# BSPD.net
KiCad netlist of a schematic drawn in Altium Designer
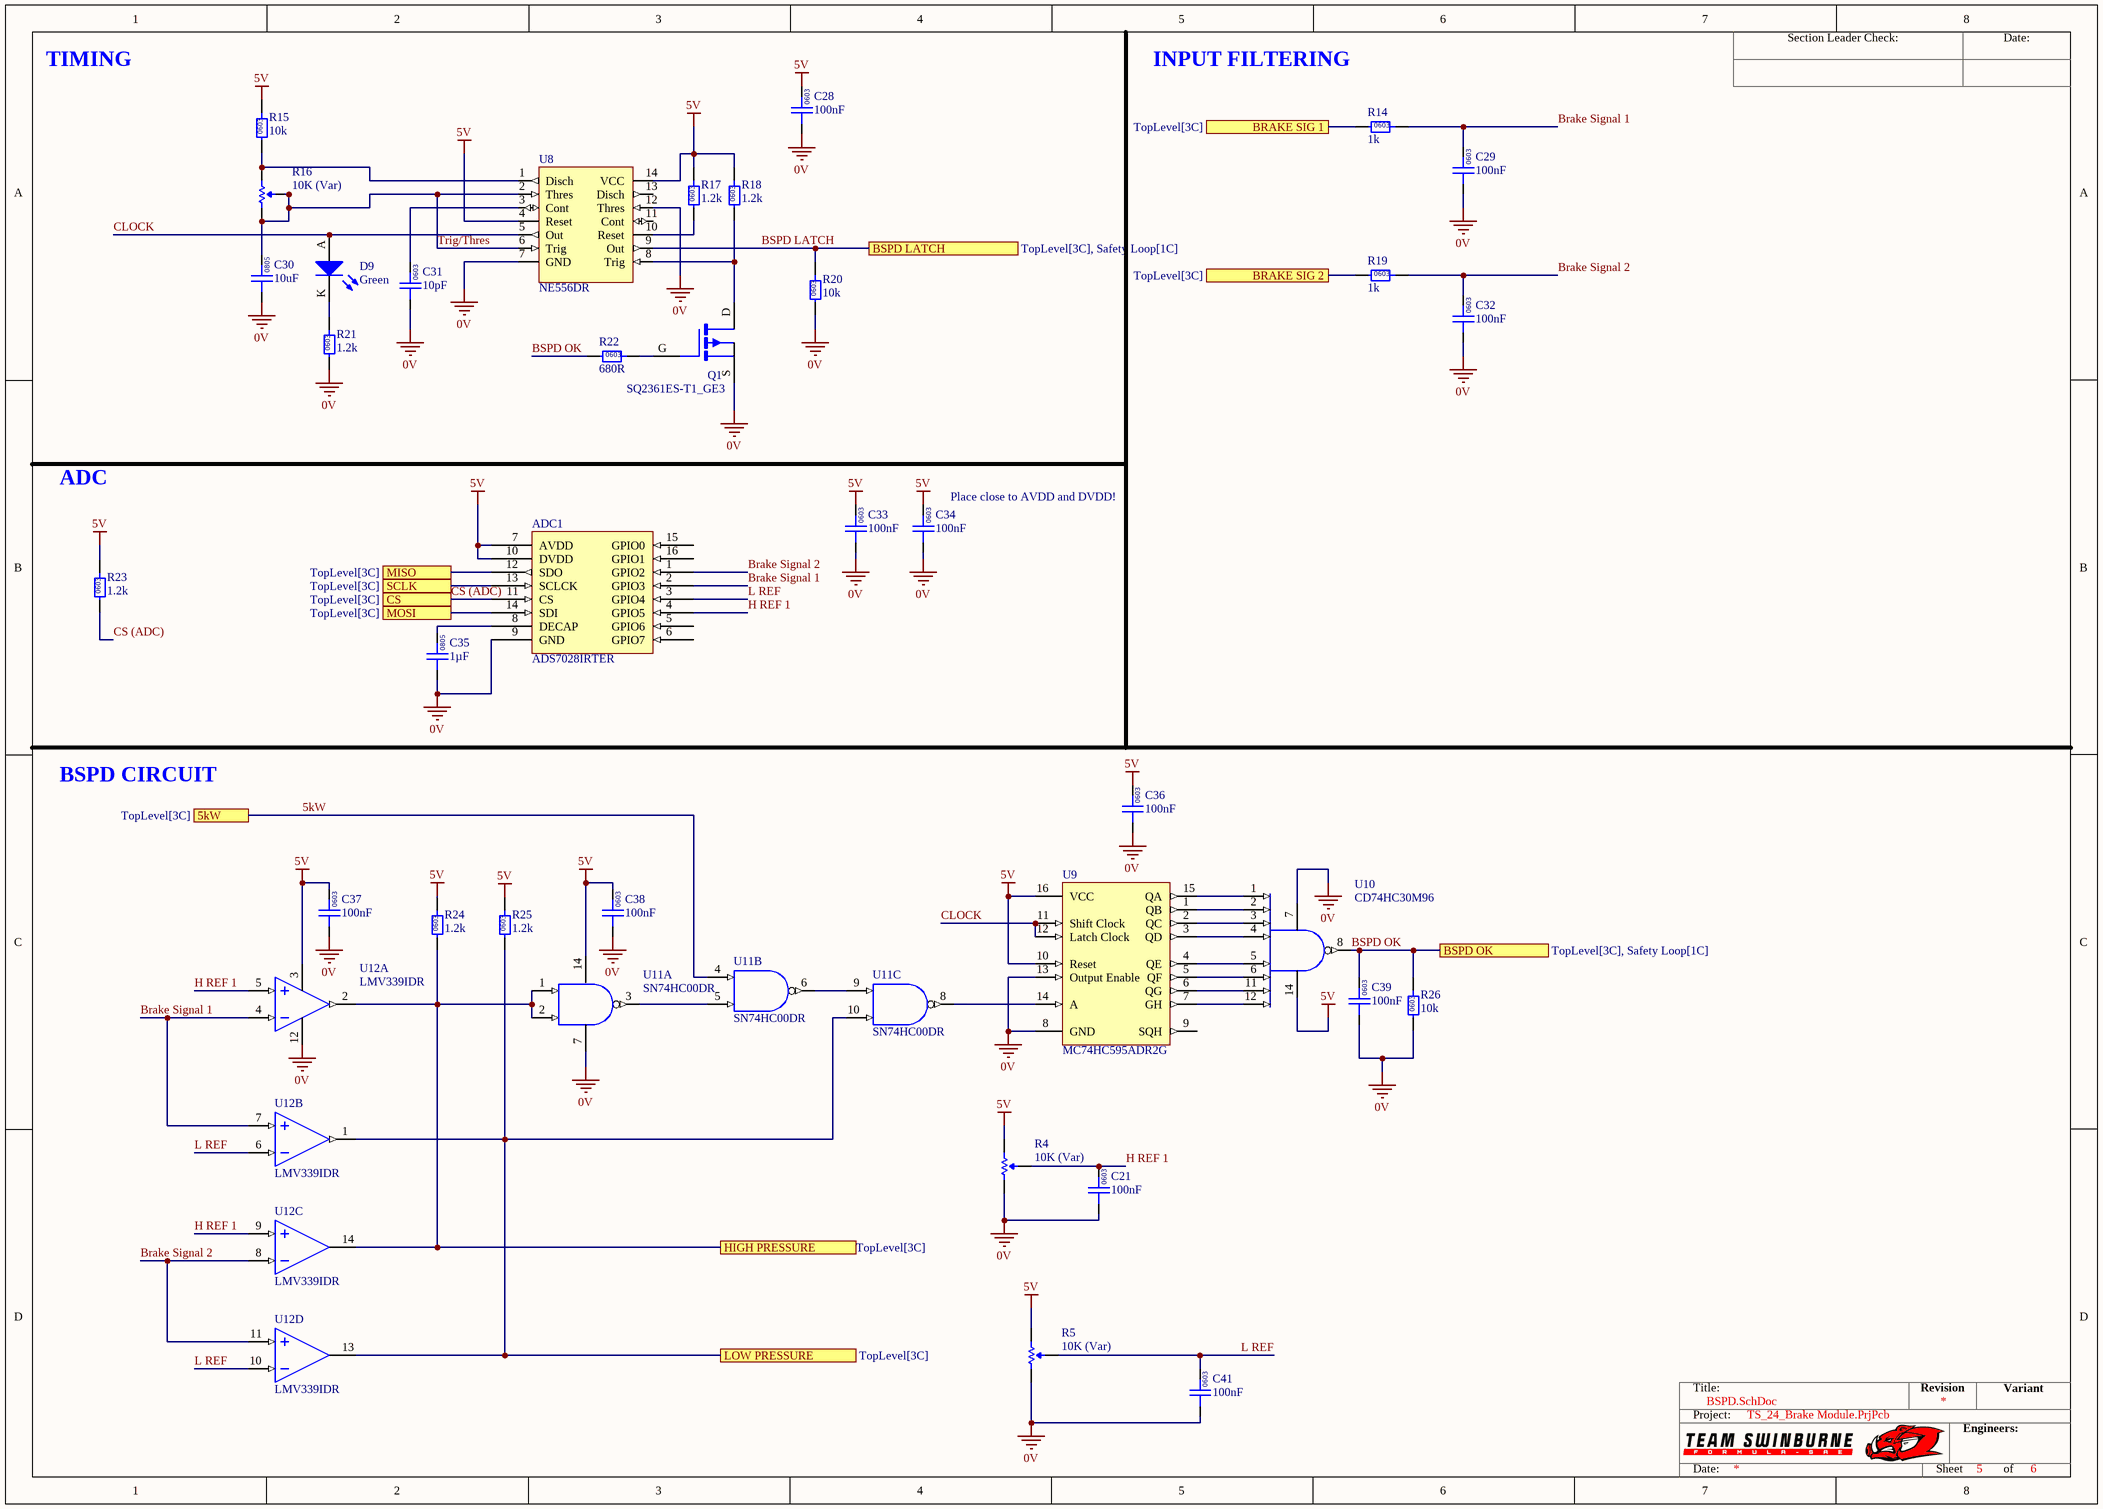
[diagram p0: BSPD.SchDoc]

(export (version "E")
  (design (tool "Eeschema 10.0.6"))
  (components
    (comp (ref "ADC1")
      (value "ADS7028IRTER")
      (footprint "WFQN-16")
      (description "IC ADC 12BIT SAR 16WQFN")
      (fields (field (name "MANUFACTURER") "Texas Instruments"))
      (libsource (lib "ts_standard_library") (part "ADS7028IRTER"))
    )
    (comp (ref "C21")
      (value "100nF")
      (footprint "0603")
      (fields
        (field (name "PART NUMBER") "GCM188L81H104KA57D")
        (field (name "MANUFACTURER") "muRata")
        (field (name "TOLERANCE") "±10%")
      )
      (libsource (lib "ts_standard_library") (part "Capacitor 0603"))
    )
    (comp (ref "C28")
      (value "100nF")
      (footprint "0603")
      (fields
        (field (name "PART NUMBER") "GCM188L81H104KA57D")
        (field (name "MANUFACTURER") "muRata")
        (field (name "TOLERANCE") "±10%")
      )
      (libsource (lib "ts_standard_library") (part "Capacitor 0603"))
    )
    (comp (ref "C29")
      (value "100nF")
      (footprint "0603")
      (fields
        (field (name "PART NUMBER") "GCM188L81H104KA57D")
        (field (name "MANUFACTURER") "muRata")
        (field (name "TOLERANCE") "±10%")
      )
      (libsource (lib "ts_standard_library") (part "Capacitor 0603"))
    )
    (comp (ref "C30")
      (value "10uF")
      (footprint "0805")
      (fields
        (field (name "PART NUMBER") "GRM21BR6YA106KE43L")
        (field (name "MANUFACTURER") "muRata")
        (field (name "TOLERANCE") "10%")
      )
      (libsource (lib "ts_standard_library") (part "Capacitor 0805"))
    )
    (comp (ref "C31")
      (value "10pF")
      (footprint "0603")
      (fields
        (field (name "PART NUMBER") "GRM1885C1H100JA01D")
        (field (name "MANUFACTURER") "Murata Electronics")
        (field (name "TOLERANCE") "±5%")
      )
      (libsource (lib "ts_standard_library") (part "Capacitor 0603"))
    )
    (comp (ref "C32")
      (value "100nF")
      (footprint "0603")
      (fields
        (field (name "PART NUMBER") "GCM188L81H104KA57D")
        (field (name "MANUFACTURER") "muRata")
        (field (name "TOLERANCE") "±10%")
      )
      (libsource (lib "ts_standard_library") (part "Capacitor 0603"))
    )
    (comp (ref "C33")
      (value "100nF")
      (footprint "0603")
      (fields
        (field (name "PART NUMBER") "GCM188L81H104KA57D")
        (field (name "MANUFACTURER") "muRata")
        (field (name "TOLERANCE") "±10%")
      )
      (libsource (lib "ts_standard_library") (part "Capacitor 0603"))
    )
    (comp (ref "C34")
      (value "100nF")
      (footprint "0603")
      (fields
        (field (name "PART NUMBER") "GCM188L81H104KA57D")
        (field (name "MANUFACTURER") "muRata")
        (field (name "TOLERANCE") "±10%")
      )
      (libsource (lib "ts_standard_library") (part "Capacitor 0603"))
    )
    (comp (ref "C35")
      (value "1µF")
      (footprint "0805")
      (fields
        (field (name "PART NUMBER") "GCM21BR71H105KA03L")
        (field (name "MANUFACTURER") "muRata")
        (field (name "TOLERANCE") "±10%")
      )
      (libsource (lib "ts_standard_library") (part "Capacitor 0805"))
    )
    (comp (ref "C36")
      (value "100nF")
      (footprint "0603")
      (fields
        (field (name "PART NUMBER") "GCM188L81H104KA57D")
        (field (name "MANUFACTURER") "muRata")
        (field (name "TOLERANCE") "±10%")
      )
      (libsource (lib "ts_standard_library") (part "Capacitor 0603"))
    )
    (comp (ref "C37")
      (value "100nF")
      (footprint "0603")
      (fields
        (field (name "PART NUMBER") "GCM188L81H104KA57D")
        (field (name "MANUFACTURER") "muRata")
        (field (name "TOLERANCE") "±10%")
      )
      (libsource (lib "ts_standard_library") (part "Capacitor 0603"))
    )
    (comp (ref "C38")
      (value "100nF")
      (footprint "0603")
      (fields
        (field (name "PART NUMBER") "GCM188L81H104KA57D")
        (field (name "MANUFACTURER") "muRata")
        (field (name "TOLERANCE") "±10%")
      )
      (libsource (lib "ts_standard_library") (part "Capacitor 0603"))
    )
    (comp (ref "C39")
      (value "100nF")
      (footprint "0603")
      (fields
        (field (name "PART NUMBER") "GCM188L81H104KA57D")
        (field (name "MANUFACTURER") "muRata")
        (field (name "TOLERANCE") "±10%")
      )
      (libsource (lib "ts_standard_library") (part "Capacitor 0603"))
    )
    (comp (ref "C41")
      (value "100nF")
      (footprint "0603")
      (fields
        (field (name "PART NUMBER") "GCM188L81H104KA57D")
        (field (name "MANUFACTURER") "muRata")
        (field (name "TOLERANCE") "±10%")
      )
      (libsource (lib "ts_standard_library") (part "Capacitor 0603"))
    )
    (comp (ref "D9")
      (value "Green")
      (footprint "0805 LED")
      (description "Green LED Indication - Discrete 1.75V 0805 (2012 Metric)")
      (fields (field (name "PART NUMBER") "SML-210FTT86") (field (name "MANUFACTURER") "ROHM Semiconductor"))
      (libsource (lib "ts_standard_library") (part "LED"))
    )
    (comp (ref "Q1")
      (value "SQ2361ES-T1_GE3")
      (footprint "VSHY SOT-23-3")
      (description "MOSFET P-CH 60V 2.8A SSOT23")
      (fields
        (field (name "MANUFACTURER") "Vishay Siliconix")
        (field (name "DIGIKEY PART NUMBER") "SQ2361ES-T1_GE3CT-ND")
        (field (name "PUBLISHER") "Altium Limited")
      )
      (libsource (lib "ts_standard_library") (part "MOSFET-P"))
    )
    (comp (ref "R4")
      (value "10K (Var)")
      (footprint "3339P-1-1103LF")
      (fields
        (field (name "PART NUMBER") "3339P-1-1103LF")
        (field (name "MANUFACTURER") "Bournes Inc")
        (field (name "TOLERANCE") "0.1")
      )
      (libsource (lib "ts_standard_library") (part "Resistor (Potentiometer)"))
    )
    (comp (ref "R5")
      (value "10K (Var)")
      (footprint "3339P-1-1103LF")
      (fields
        (field (name "PART NUMBER") "3339P-1-1103LF")
        (field (name "MANUFACTURER") "Bournes Inc")
        (field (name "TOLERANCE") "0.1")
      )
      (libsource (lib "ts_standard_library") (part "Resistor (Potentiometer)"))
    )
    (comp (ref "R14")
      (value "1k")
      (footprint "0603")
      (fields
        (field (name "PART NUMBER") "RC0603FR-071KL")
        (field (name "MANUFACTURER") "YAGEO")
        (field (name "TOLERANCE") "0.01")
      )
      (libsource (lib "ts_standard_library") (part "Resistor 0603"))
    )
    (comp (ref "R15")
      (value "10k")
      (footprint "0603")
      (fields
        (field (name "PART NUMBER") "RC0603FR-0710KL")
        (field (name "MANUFACTURER") "YAGEO")
        (field (name "TOLERANCE") "0.01")
      )
      (libsource (lib "ts_standard_library") (part "Resistor 0603"))
    )
    (comp (ref "R16")
      (value "10K (Var)")
      (footprint "B 3296")
      (fields
        (field (name "PART NUMBER") "3296W-1-103LF")
        (field (name "MANUFACTURER") "Bournes Inc")
        (field (name "TOLERANCE") "0.1")
      )
      (libsource (lib "ts_standard_library") (part "Resistor (Potentiometer)"))
    )
    (comp (ref "R17")
      (value "1.2k")
      (footprint "0603")
      (fields
        (field (name "PART NUMBER") "RC0603JR-071K2L")
        (field (name "MANUFACTURER") "YAGEO")
        (field (name "TOLERANCE") "0.01")
      )
      (libsource (lib "ts_standard_library") (part "Resistor 0603"))
    )
    (comp (ref "R18")
      (value "1.2k")
      (footprint "0603")
      (fields
        (field (name "PART NUMBER") "RC0603JR-071K2L")
        (field (name "MANUFACTURER") "YAGEO")
        (field (name "TOLERANCE") "0.01")
      )
      (libsource (lib "ts_standard_library") (part "Resistor 0603"))
    )
    (comp (ref "R19")
      (value "1k")
      (footprint "0603")
      (fields
        (field (name "PART NUMBER") "RC0603FR-071KL")
        (field (name "MANUFACTURER") "YAGEO")
        (field (name "TOLERANCE") "0.01")
      )
      (libsource (lib "ts_standard_library") (part "Resistor 0603"))
    )
    (comp (ref "R20")
      (value "10k")
      (footprint "0603")
      (fields
        (field (name "PART NUMBER") "RC0603FR-0710KL")
        (field (name "MANUFACTURER") "YAGEO")
        (field (name "TOLERANCE") "0.01")
      )
      (libsource (lib "ts_standard_library") (part "Resistor 0603"))
    )
    (comp (ref "R21")
      (value "1.2k")
      (footprint "0603")
      (fields
        (field (name "PART NUMBER") "RC0603JR-071K2L")
        (field (name "MANUFACTURER") "YAGEO")
        (field (name "TOLERANCE") "0.01")
      )
      (libsource (lib "ts_standard_library") (part "Resistor 0603"))
    )
    (comp (ref "R22")
      (value "680R")
      (footprint "0603")
      (fields
        (field (name "PART NUMBER") "RC0603JR-13680RL")
        (field (name "MANUFACTURER") "YAGEO")
        (field (name "TOLERANCE") "0.01")
      )
      (libsource (lib "ts_standard_library") (part "Resistor 0603"))
    )
    (comp (ref "R23")
      (value "1.2k")
      (footprint "0603")
      (fields
        (field (name "PART NUMBER") "RC0603JR-071K2L")
        (field (name "MANUFACTURER") "YAGEO")
        (field (name "TOLERANCE") "0.01")
      )
      (libsource (lib "ts_standard_library") (part "Resistor 0603"))
    )
    (comp (ref "R24")
      (value "1.2k")
      (footprint "0603")
      (fields
        (field (name "PART NUMBER") "RC0603JR-071K2L")
        (field (name "MANUFACTURER") "YAGEO")
        (field (name "TOLERANCE") "0.01")
      )
      (libsource (lib "ts_standard_library") (part "Resistor 0603"))
    )
    (comp (ref "R25")
      (value "1.2k")
      (footprint "0603")
      (fields
        (field (name "PART NUMBER") "RC0603JR-071K2L")
        (field (name "MANUFACTURER") "YAGEO")
        (field (name "TOLERANCE") "0.01")
      )
      (libsource (lib "ts_standard_library") (part "Resistor 0603"))
    )
    (comp (ref "R26")
      (value "10k")
      (footprint "0603")
      (fields
        (field (name "PART NUMBER") "RC0603FR-0710KL")
        (field (name "MANUFACTURER") "YAGEO")
        (field (name "TOLERANCE") "0.01")
      )
      (libsource (lib "ts_standard_library") (part "Resistor 0603"))
    )
    (comp (ref "U8")
      (value "NE556DR")
      (footprint "TI-SOIC14")
      (description "IC OSC TIMER DUAL 100KHZ 14SOIC")
      (fields
        (field (name "MANUFACTURER") "Texas Instruments")
        (field (name "DIGIKEY PART NUMBER") "296-26240-1-ND")
      )
      (libsource (lib "ts_standard_library") (part "NE556DR"))
    )
    (comp (ref "U9")
      (value "MC74HC595ADR2G")
      (footprint "ON 16-SOIC")
      (description "IC SHIFT REGISTR 8BIT 3ST 16SOIC")
      (libsource (lib "Team Swinburne") (part "MC74HC595ADR2G"))
    )
    (comp (ref "U10")
      (value "CD74HC30M96")
      (footprint "TI 14-SOIC")
      (description "IC GATE NAND 1CH 8-INP 14SOIC")
      (libsource (lib "Team Swinburne") (part "CD74HC30M96"))
    )
    (comp (ref "U11")
      (value "SN74HC00DR")
      (footprint "TI 14-SOIC")
      (description "NAND Gate IC 4 Channel 14-SOIC")
      (libsource (lib "Team Swinburne") (part "SN74HC00DR"))
    )
    (comp (ref "U12")
      (value "LMV339IDR")
      (footprint "TI 14-SOIC")
      (description "Comparator General Purpose Open Collector 14-SOIC")
      (libsource (lib "Team Swinburne") (part "LMV339IDR"))
    )
  )
  (nets
    (net (code "1") (name "/5kW") (class "Default")
      (node (ref "U11") (pin "4") (pinfunction "2A_4") (pintype "input"))
    )
    (net (code "2") (name "/BRAKE SIG 1") (class "Default")
      (node (ref "R14") (pin "1") (pinfunction "1_1") (pintype "passive"))
    )
    (net (code "3") (name "/BRAKE SIG 2") (class "Default")
      (node (ref "R19") (pin "1") (pinfunction "1_1") (pintype "passive"))
    )
    (net (code "4") (name "/BSPD LATCH") (class "Default")
      (node (ref "R20") (pin "2") (pinfunction "2_2") (pintype "passive"))
      (node (ref "U8") (pin "9") (pinfunction "Out_9") (pintype "output"))
    )
    (net (code "5") (name "/BSPD OK") (class "Default")
      (node (ref "C39") (pin "2") (pinfunction "2_2") (pintype "passive"))
      (node (ref "R22") (pin "1") (pinfunction "1_1") (pintype "passive"))
      (node (ref "R26") (pin "2") (pinfunction "2_2") (pintype "passive"))
      (node (ref "U10") (pin "8") (pinfunction "Output_8") (pintype "output"))
    )
    (net (code "6") (name "/Brake Signal 1") (class "Default")
      (node (ref "ADC1") (pin "2") (pinfunction "GPIO3_2") (pintype "input"))
      (node (ref "C29") (pin "2") (pinfunction "2_2") (pintype "passive"))
      (node (ref "R14") (pin "2") (pinfunction "2_2") (pintype "passive"))
      (node (ref "U12") (pin "4") (pinfunction "IN_A-_4") (pintype "input"))
      (node (ref "U12") (pin "7") (pinfunction "IN_B+_7") (pintype "input"))
    )
    (net (code "7") (name "/Brake Signal 2") (class "Default")
      (node (ref "ADC1") (pin "1") (pinfunction "GPIO2_1") (pintype "input"))
      (node (ref "C32") (pin "2") (pinfunction "2_2") (pintype "passive"))
      (node (ref "R19") (pin "2") (pinfunction "2_2") (pintype "passive"))
      (node (ref "U12") (pin "11") (pinfunction "IN_D+_11") (pintype "input"))
      (node (ref "U12") (pin "8") (pinfunction "IN_C-_8") (pintype "input"))
    )
    (net (code "8") (name "/CLOCK") (class "Default")
      (node (ref "D9") (pin "A") (pinfunction "A_A") (pintype "passive"))
      (node (ref "U8") (pin "5") (pinfunction "Out_5") (pintype "output"))
      (node (ref "U9") (pin "11") (pinfunction "Shift_Clock_11") (pintype "input"))
      (node (ref "U9") (pin "12") (pinfunction "Latch_Clock_12") (pintype "input"))
    )
    (net (code "9") (name "/CS (ADC)") (class "Default")
      (node (ref "ADC1") (pin "11") (pinfunction "CS_11") (pintype "input"))
      (node (ref "R23") (pin "1") (pinfunction "1_1") (pintype "passive"))
    )
    (net (code "10") (name "/H REF 1") (class "Default")
      (node (ref "ADC1") (pin "4") (pinfunction "GPIO5_4") (pintype "input"))
      (node (ref "C21") (pin "2") (pinfunction "2_2") (pintype "passive"))
      (node (ref "R4") (pin "2") (pinfunction "Wiper_2") (pintype "passive"))
      (node (ref "U12") (pin "5") (pinfunction "IN_A+_5") (pintype "input"))
      (node (ref "U12") (pin "9") (pinfunction "IN_C+_9") (pintype "input"))
    )
    (net (code "11") (name "/HIGH PRESSURE") (class "Default")
      (node (ref "R24") (pin "1") (pinfunction "1_1") (pintype "passive"))
      (node (ref "U11") (pin "1") (pinfunction "1A_1") (pintype "input"))
      (node (ref "U11") (pin "2") (pinfunction "1B_2") (pintype "input"))
      (node (ref "U12") (pin "14") (pinfunction "OUT_C_14") (pintype "passive"))
      (node (ref "U12") (pin "2") (pinfunction "OUT_A_2") (pintype "output"))
    )
    (net (code "12") (name "/L REF") (class "Default")
      (node (ref "ADC1") (pin "3") (pinfunction "GPIO4_3") (pintype "input"))
      (node (ref "C41") (pin "2") (pinfunction "2_2") (pintype "passive"))
      (node (ref "R5") (pin "2") (pinfunction "Wiper_2") (pintype "passive"))
      (node (ref "U12") (pin "10") (pinfunction "IN_D-_10") (pintype "input"))
      (node (ref "U12") (pin "6") (pinfunction "IN_B-_6") (pintype "input"))
    )
    (net (code "13") (name "/LOW PRESSURE") (class "Default")
      (node (ref "R25") (pin "1") (pinfunction "1_1") (pintype "passive"))
      (node (ref "U11") (pin "10") (pinfunction "3B_10") (pintype "input"))
      (node (ref "U12") (pin "1") (pinfunction "OUT_B_1") (pintype "output"))
      (node (ref "U12") (pin "13") (pinfunction "OUT_D_13") (pintype "passive"))
    )
    (net (code "14") (name "/MISO") (class "Default")
      (node (ref "ADC1") (pin "12") (pinfunction "SDO_12") (pintype "output"))
    )
    (net (code "15") (name "/MOSI") (class "Default")
      (node (ref "ADC1") (pin "14") (pinfunction "SDI_14") (pintype "input"))
    )
    (net (code "16") (name "/SCLK") (class "Default")
      (node (ref "ADC1") (pin "13") (pinfunction "SCLCK_13") (pintype "input"))
    )
    (net (code "17") (name "/Trig{slash}Thres") (class "Default")
      (node (ref "C30") (pin "2") (pinfunction "2_2") (pintype "passive"))
      (node (ref "R16") (pin "2") (pinfunction "Wiper_2") (pintype "passive"))
      (node (ref "R16") (pin "3") (pinfunction "CW_3") (pintype "passive"))
      (node (ref "U8") (pin "2") (pinfunction "Thres_2") (pintype "input"))
      (node (ref "U8") (pin "6") (pinfunction "Trig_6") (pintype "input"))
    )
    (net (code "18") (name "0V") (class "Default")
      (node (ref "ADC1") (pin "9") (pinfunction "GND_9") (pintype "power_in"))
      (node (ref "C21") (pin "1") (pinfunction "1_1") (pintype "passive"))
      (node (ref "C28") (pin "1") (pinfunction "1_1") (pintype "passive"))
      (node (ref "C29") (pin "1") (pinfunction "1_1") (pintype "passive"))
      (node (ref "C30") (pin "1") (pinfunction "1_1") (pintype "passive"))
      (node (ref "C31") (pin "1") (pinfunction "1_1") (pintype "passive"))
      (node (ref "C32") (pin "1") (pinfunction "1_1") (pintype "passive"))
      (node (ref "C33") (pin "1") (pinfunction "1_1") (pintype "passive"))
      (node (ref "C34") (pin "1") (pinfunction "1_1") (pintype "passive"))
      (node (ref "C35") (pin "1") (pinfunction "1_1") (pintype "passive"))
      (node (ref "C36") (pin "1") (pinfunction "1_1") (pintype "passive"))
      (node (ref "C37") (pin "1") (pinfunction "1_1") (pintype "passive"))
      (node (ref "C38") (pin "1") (pinfunction "1_1") (pintype "passive"))
      (node (ref "C39") (pin "1") (pinfunction "1_1") (pintype "passive"))
      (node (ref "C41") (pin "1") (pinfunction "1_1") (pintype "passive"))
      (node (ref "Q1") (pin "S") (pinfunction "S_S") (pintype "passive"))
      (node (ref "R20") (pin "1") (pinfunction "1_1") (pintype "passive"))
      (node (ref "R21") (pin "1") (pinfunction "1_1") (pintype "passive"))
      (node (ref "R26") (pin "1") (pinfunction "1_1") (pintype "passive"))
      (node (ref "R4") (pin "3") (pinfunction "CW_3") (pintype "passive"))
      (node (ref "R5") (pin "3") (pinfunction "CW_3") (pintype "passive"))
      (node (ref "U10") (pin "7") (pinfunction "GND_7") (pintype "power_in"))
      (node (ref "U11") (pin "7") (pinfunction "GND_7") (pintype "power_in"))
      (node (ref "U12") (pin "12") (pinfunction "V-_12") (pintype "power_in"))
      (node (ref "U8") (pin "12") (pinfunction "Thres_12") (pintype "input"))
      (node (ref "U8") (pin "7") (pinfunction "GND_7") (pintype "power_in"))
      (node (ref "U9") (pin "13") (pinfunction "Output_Enable_13") (pintype "input"))
      (node (ref "U9") (pin "8") (pinfunction "GND_8") (pintype "power_in"))
    )
    (net (code "19") (name "5V") (class "Default")
      (node (ref "ADC1") (pin "10") (pinfunction "DVDD_10") (pintype "power_in"))
      (node (ref "ADC1") (pin "7") (pinfunction "AVDD_7") (pintype "power_in"))
      (node (ref "C28") (pin "2") (pinfunction "2_2") (pintype "passive"))
      (node (ref "C33") (pin "2") (pinfunction "2_2") (pintype "passive"))
      (node (ref "C34") (pin "2") (pinfunction "2_2") (pintype "passive"))
      (node (ref "C36") (pin "2") (pinfunction "2_2") (pintype "passive"))
      (node (ref "C37") (pin "2") (pinfunction "2_2") (pintype "passive"))
      (node (ref "C38") (pin "2") (pinfunction "2_2") (pintype "passive"))
      (node (ref "R15") (pin "2") (pinfunction "2_2") (pintype "passive"))
      (node (ref "R17") (pin "2") (pinfunction "2_2") (pintype "passive"))
      (node (ref "R18") (pin "2") (pinfunction "2_2") (pintype "passive"))
      (node (ref "R23") (pin "2") (pinfunction "2_2") (pintype "passive"))
      (node (ref "R24") (pin "2") (pinfunction "2_2") (pintype "passive"))
      (node (ref "R25") (pin "2") (pinfunction "2_2") (pintype "passive"))
      (node (ref "R4") (pin "1") (pinfunction "CCW_1") (pintype "passive"))
      (node (ref "R5") (pin "1") (pinfunction "CCW_1") (pintype "passive"))
      (node (ref "U10") (pin "14") (pinfunction "VCC_14") (pintype "power_in"))
      (node (ref "U11") (pin "14") (pinfunction "VCC_14") (pintype "power_in"))
      (node (ref "U12") (pin "3") (pinfunction "V+_3") (pintype "power_in"))
      (node (ref "U8") (pin "14") (pinfunction "VCC_14") (pintype "passive"))
      (node (ref "U8") (pin "4") (pinfunction "Reset_4") (pintype "passive"))
      (node (ref "U9") (pin "10") (pinfunction "Reset_10") (pintype "input"))
      (node (ref "U9") (pin "16") (pinfunction "VCC_16") (pintype "power_in"))
    )
    (net (code "20") (name "Net-(ADC1-DECAP)") (class "Default")
      (node (ref "ADC1") (pin "8") (pinfunction "DECAP_8") (pintype "power_in"))
      (node (ref "C35") (pin "2") (pinfunction "2_2") (pintype "passive"))
    )
    (net (code "21") (name "Net-(C31-Pad2)") (class "Default")
      (node (ref "C31") (pin "2") (pinfunction "2_2") (pintype "passive"))
      (node (ref "U8") (pin "3") (pinfunction "Cont_3") (pintype "bidirectional"))
    )
    (net (code "22") (name "Net-(D9-PadK)") (class "Default")
      (node (ref "D9") (pin "K") (pinfunction "K_K") (pintype "passive"))
      (node (ref "R21") (pin "2") (pinfunction "2_2") (pintype "passive"))
    )
    (net (code "23") (name "Net-(Q1-PadD)") (class "Default")
      (node (ref "Q1") (pin "D") (pinfunction "D_D") (pintype "passive"))
      (node (ref "R18") (pin "1") (pinfunction "1_1") (pintype "passive"))
      (node (ref "U8") (pin "8") (pinfunction "Trig_8") (pintype "input"))
    )
    (net (code "24") (name "Net-(Q1-PadG)") (class "Default")
      (node (ref "Q1") (pin "G") (pinfunction "G_G") (pintype "passive"))
      (node (ref "R22") (pin "2") (pinfunction "2_2") (pintype "passive"))
    )
    (net (code "25") (name "Net-(R16-CCW)") (class "Default")
      (node (ref "R15") (pin "1") (pinfunction "1_1") (pintype "passive"))
      (node (ref "R16") (pin "1") (pinfunction "CCW_1") (pintype "passive"))
      (node (ref "U8") (pin "1") (pinfunction "Disch_1") (pintype "output"))
    )
    (net (code "26") (name "Net-(R17-Pad1)") (class "Default")
      (node (ref "R17") (pin "1") (pinfunction "1_1") (pintype "passive"))
      (node (ref "U8") (pin "10") (pinfunction "Reset_10") (pintype "passive"))
    )
    (net (code "27") (name "Net-(U9-GH)") (class "Default")
      (node (ref "U10") (pin "12") (pinfunction "Input_12") (pintype "input"))
      (node (ref "U9") (pin "7") (pinfunction "GH_7") (pintype "output"))
    )
    (net (code "28") (name "Net-(U9-QA)") (class "Default")
      (node (ref "U10") (pin "1") (pinfunction "Input_1") (pintype "input"))
      (node (ref "U9") (pin "15") (pinfunction "QA_15") (pintype "output"))
    )
    (net (code "29") (name "Net-(U9-QB)") (class "Default")
      (node (ref "U10") (pin "2") (pinfunction "Input_2") (pintype "input"))
      (node (ref "U9") (pin "1") (pinfunction "QB_1") (pintype "output"))
    )
    (net (code "30") (name "Net-(U9-QC)") (class "Default")
      (node (ref "U10") (pin "3") (pinfunction "Input_3") (pintype "input"))
      (node (ref "U9") (pin "2") (pinfunction "QC_2") (pintype "output"))
    )
    (net (code "31") (name "Net-(U9-QD)") (class "Default")
      (node (ref "U10") (pin "4") (pinfunction "Input_4") (pintype "input"))
      (node (ref "U9") (pin "3") (pinfunction "QD_3") (pintype "output"))
    )
    (net (code "32") (name "Net-(U9-QE)") (class "Default")
      (node (ref "U10") (pin "5") (pinfunction "Input_5") (pintype "input"))
      (node (ref "U9") (pin "4") (pinfunction "QE_4") (pintype "output"))
    )
    (net (code "33") (name "Net-(U9-QF)") (class "Default")
      (node (ref "U10") (pin "6") (pinfunction "Input_6") (pintype "input"))
      (node (ref "U9") (pin "5") (pinfunction "QF_5") (pintype "output"))
    )
    (net (code "34") (name "Net-(U9-QG)") (class "Default")
      (node (ref "U10") (pin "11") (pinfunction "Input_11") (pintype "input"))
      (node (ref "U9") (pin "6") (pinfunction "QG_6") (pintype "output"))
    )
    (net (code "35") (name "Net-(U11A-1Y)") (class "Default")
      (node (ref "U11") (pin "3") (pinfunction "1Y_3") (pintype "output"))
      (node (ref "U11") (pin "5") (pinfunction "2B_5") (pintype "input"))
    )
    (net (code "36") (name "Net-(U11B-2Y)") (class "Default")
      (node (ref "U11") (pin "6") (pinfunction "2Y_6") (pintype "output"))
      (node (ref "U11") (pin "9") (pinfunction "3A_9") (pintype "input"))
    )
    (net (code "37") (name "Net-(U11C-3Y)") (class "Default")
      (node (ref "U11") (pin "8") (pinfunction "3Y_8") (pintype "output"))
      (node (ref "U9") (pin "14") (pinfunction "A_14") (pintype "input"))
    )
    (net (code "38") (name "unconnected-(ADC1-GPIO0-Pad15)") (class "Default")
      (node (ref "ADC1") (pin "15") (pinfunction "GPIO0_15") (pintype "input"))
    )
    (net (code "39") (name "unconnected-(ADC1-GPIO1-Pad16)") (class "Default")
      (node (ref "ADC1") (pin "16") (pinfunction "GPIO1_16") (pintype "input"))
    )
    (net (code "40") (name "unconnected-(ADC1-GPIO6-Pad5)") (class "Default")
      (node (ref "ADC1") (pin "5") (pinfunction "GPIO6_5") (pintype "input"))
    )
    (net (code "41") (name "unconnected-(ADC1-GPIO7-Pad6)") (class "Default")
      (node (ref "ADC1") (pin "6") (pinfunction "GPIO7_6") (pintype "input"))
    )
    (net (code "42") (name "unconnected-(U8-Cont-Pad11)") (class "Default")
      (node (ref "U8") (pin "11") (pinfunction "Cont_11") (pintype "bidirectional"))
    )
    (net (code "43") (name "unconnected-(U8-Disch-Pad13)") (class "Default")
      (node (ref "U8") (pin "13") (pinfunction "Disch_13") (pintype "output"))
    )
    (net (code "44") (name "unconnected-(U9-SQH-Pad9)") (class "Default")
      (node (ref "U9") (pin "9") (pinfunction "SQH_9") (pintype "output"))
    )
  )
)
